# AUDIO_ETHNET.net
KiCad netlist of a schematic drawn in Altium Designer
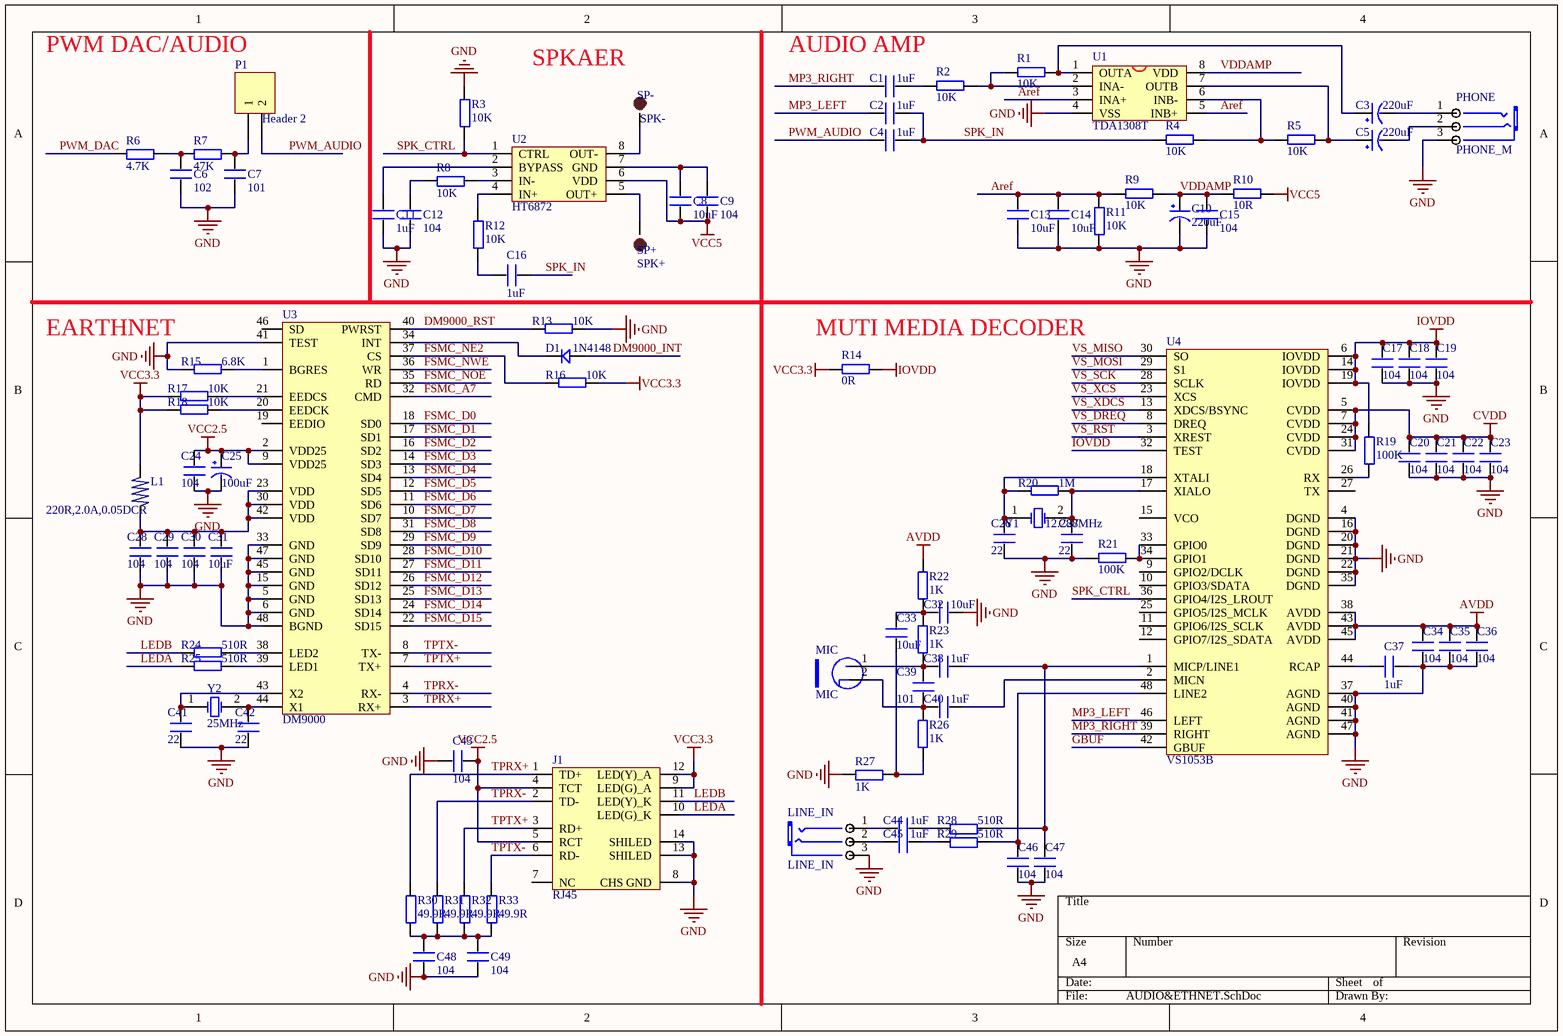
[diagram p0: AUDIO&ETHNET.SchDoc]

(export (version "E")
  (design (tool "Eeschema 10.0.6"))
  (components
    (comp (ref "C1") (value "1uF") (footprint "0603P") (libsource (lib "WarShip V3 STM32103封装库") (part "C")))
    (comp (ref "C2") (value "1uF") (footprint "0603P") (libsource (lib "WarShip V3 STM32103封装库") (part "C")))
    (comp (ref "C3")
      (value "220uF")
      (footprint "CC6.56.5")
      (libsource (lib "WarShip V3 STM32103封装库") (part "CAP"))
    )
    (comp (ref "C4") (value "1uF") (footprint "0603P") (libsource (lib "WarShip V3 STM32103封装库") (part "C")))
    (comp (ref "C5")
      (value "220uF")
      (footprint "CC6.56.5")
      (libsource (lib "WarShip V3 STM32103封装库") (part "CAP"))
    )
    (comp (ref "C6") (value "102") (footprint "0603P") (libsource (lib "WarShip V3 STM32103封装库") (part "C")))
    (comp (ref "C7") (value "101") (footprint "0603P") (libsource (lib "WarShip V3 STM32103封装库") (part "C")))
    (comp (ref "C8") (value "10uF") (footprint "0603P") (libsource (lib "WarShip V3 STM32103封装库") (part "C")))
    (comp (ref "C9") (value "104") (footprint "0603P") (libsource (lib "WarShip V3 STM32103封装库") (part "C")))
    (comp (ref "C10") (value "220uF") (footprint "CC6.56.5") (libsource (lib "") (part "CAP_1")))
    (comp (ref "C11") (value "1uF") (footprint "0603P") (libsource (lib "WarShip V3 STM32103封装库") (part "C")))
    (comp (ref "C12") (value "104") (footprint "0603P") (libsource (lib "WarShip V3 STM32103封装库") (part "C")))
    (comp (ref "C13")
      (value "10uF")
      (footprint "0603P")
      (libsource (lib "WarShip V3 STM32103封装库") (part "C"))
    )
    (comp (ref "C14")
      (value "10uF")
      (footprint "0603P")
      (libsource (lib "WarShip V3 STM32103封装库") (part "C"))
    )
    (comp (ref "C15") (value "104") (footprint "0603P") (libsource (lib "WarShip V3 STM32103封装库") (part "C")))
    (comp (ref "C16") (value "1uF") (footprint "0603P") (libsource (lib "WarShip V3 STM32103封装库") (part "C")))
    (comp (ref "C17") (value "104") (footprint "0603P") (libsource (lib "WarShip V3 STM32103封装库") (part "C")))
    (comp (ref "C18") (value "104") (footprint "0603P") (libsource (lib "WarShip V3 STM32103封装库") (part "C")))
    (comp (ref "C19") (value "104") (footprint "0603P") (libsource (lib "WarShip V3 STM32103封装库") (part "C")))
    (comp (ref "C20") (value "104") (footprint "0603P") (libsource (lib "WarShip V3 STM32103封装库") (part "C")))
    (comp (ref "C21") (value "104") (footprint "0603P") (libsource (lib "WarShip V3 STM32103封装库") (part "C")))
    (comp (ref "C22") (value "104") (footprint "0603P") (libsource (lib "WarShip V3 STM32103封装库") (part "C")))
    (comp (ref "C23") (value "104") (footprint "0603P") (libsource (lib "WarShip V3 STM32103封装库") (part "C")))
    (comp (ref "C24") (value "104") (footprint "0603P") (libsource (lib "WarShip V3 STM32103封装库") (part "C")))
    (comp (ref "C25") (value "100uF") (footprint "CC6.56.5") (libsource (lib "") (part "CAP_1")))
    (comp (ref "C26") (value "22") (footprint "0603P") (libsource (lib "WarShip V3 STM32103封装库") (part "C")))
    (comp (ref "C27") (value "22") (footprint "0603P") (libsource (lib "WarShip V3 STM32103封装库") (part "C")))
    (comp (ref "C28") (value "104") (footprint "0603P") (libsource (lib "WarShip V3 STM32103封装库") (part "C")))
    (comp (ref "C29") (value "104") (footprint "0603P") (libsource (lib "WarShip V3 STM32103封装库") (part "C")))
    (comp (ref "C30") (value "104") (footprint "0603P") (libsource (lib "WarShip V3 STM32103封装库") (part "C")))
    (comp (ref "C31")
      (value "10uF")
      (footprint "0603P")
      (libsource (lib "WarShip V3 STM32103封装库") (part "C"))
    )
    (comp (ref "C32")
      (value "10uF")
      (footprint "0603P")
      (libsource (lib "WarShip V3 STM32103封装库") (part "C"))
    )
    (comp (ref "C33")
      (value "10uF")
      (footprint "0603P")
      (libsource (lib "WarShip V3 STM32103封装库") (part "C"))
    )
    (comp (ref "C34") (value "104") (footprint "0603P") (libsource (lib "WarShip V3 STM32103封装库") (part "C")))
    (comp (ref "C35") (value "104") (footprint "0603P") (libsource (lib "WarShip V3 STM32103封装库") (part "C")))
    (comp (ref "C36") (value "104") (footprint "0603P") (libsource (lib "WarShip V3 STM32103封装库") (part "C")))
    (comp (ref "C37") (value "1uF") (footprint "0603P") (libsource (lib "WarShip V3 STM32103封装库") (part "C")))
    (comp (ref "C38") (value "1uF") (footprint "0603P") (libsource (lib "WarShip V3 STM32103封装库") (part "C")))
    (comp (ref "C39") (value "101") (footprint "0603P") (libsource (lib "WarShip V3 STM32103封装库") (part "C")))
    (comp (ref "C40") (value "1uF") (footprint "0603P") (libsource (lib "WarShip V3 STM32103封装库") (part "C")))
    (comp (ref "C41") (value "22") (footprint "0603P") (libsource (lib "WarShip V3 STM32103封装库") (part "C")))
    (comp (ref "C42") (value "22") (footprint "0603P") (libsource (lib "WarShip V3 STM32103封装库") (part "C")))
    (comp (ref "C43") (value "104") (footprint "0603P") (libsource (lib "WarShip V3 STM32103封装库") (part "C")))
    (comp (ref "C44") (value "1uF") (footprint "0603P") (libsource (lib "WarShip V3 STM32103封装库") (part "C")))
    (comp (ref "C45") (value "1uF") (footprint "0603P") (libsource (lib "WarShip V3 STM32103封装库") (part "C")))
    (comp (ref "C46") (value "104") (footprint "0603P") (libsource (lib "WarShip V3 STM32103封装库") (part "C")))
    (comp (ref "C47") (value "104") (footprint "0603P") (libsource (lib "WarShip V3 STM32103封装库") (part "C")))
    (comp (ref "C48") (value "104") (footprint "0603P") (libsource (lib "WarShip V3 STM32103封装库") (part "C")))
    (comp (ref "C49") (value "104") (footprint "0603P") (libsource (lib "WarShip V3 STM32103封装库") (part "C")))
    (comp (ref "D1")
      (value "1N4148")
      (footprint "DIODE_SOP")
      (libsource (lib "WarShip V3 STM32103封装库") (part "D"))
    )
    (comp (ref "J1")
      (value "RJ45")
      (footprint "HR911105A")
      (libsource (lib "WarShip V3 STM32103封装库") (part "HR911105"))
    )
    (comp (ref "L1")
      (value "220R,2.0A,0.05DCR")
      (footprint "0603P")
      (libsource (lib "WarShip V3 STM32103封装库") (part "L"))
    )
    (comp (ref "LINE_IN")
      (value "LINE_IN")
      (footprint "PHONE_ST")
      (libsource (lib "WarShip V3 STM32103封装库") (part "PHONE_M"))
    )
    (comp (ref "MIC")
      (value "MIC")
      (footprint "MIC-6022")
      (libsource (lib "WarShip V3 STM32103封装库") (part "MIC"))
    )
    (comp (ref "P1")
      (value "Header 2")
      (footprint "HDR1X2")
      (description "Header, 2-Pin")
      (fields (field (name "PUBLISHER") "Altium Limited"))
      (libsource (lib "WarShip V3 STM32103封装库") (part "Header 2"))
    )
    (comp (ref "PHONE") (value "PHONE_M") (footprint "PHONE_ST") (libsource (lib "") (part "PHONE_M_1")))
    (comp (ref "R1") (value "10K") (footprint "0603P") (libsource (lib "WarShip V3 STM32103封装库") (part "R")))
    (comp (ref "R2") (value "10K") (footprint "0603P") (libsource (lib "WarShip V3 STM32103封装库") (part "R")))
    (comp (ref "R3") (value "10K") (footprint "0603P") (libsource (lib "WarShip V3 STM32103封装库") (part "R")))
    (comp (ref "R4") (value "10K") (footprint "0603P") (libsource (lib "WarShip V3 STM32103封装库") (part "R")))
    (comp (ref "R5") (value "10K") (footprint "0603P") (libsource (lib "WarShip V3 STM32103封装库") (part "R")))
    (comp (ref "R6") (value "4.7K") (footprint "0603P") (libsource (lib "WarShip V3 STM32103封装库") (part "R")))
    (comp (ref "R7") (value "47K") (footprint "0603P") (libsource (lib "WarShip V3 STM32103封装库") (part "R")))
    (comp (ref "R8") (value "10K") (footprint "0603P") (libsource (lib "WarShip V3 STM32103封装库") (part "R")))
    (comp (ref "R9") (value "10K") (footprint "0603P") (libsource (lib "WarShip V3 STM32103封装库") (part "R")))
    (comp (ref "R10") (value "10R") (footprint "0603P") (libsource (lib "WarShip V3 STM32103封装库") (part "R")))
    (comp (ref "R11") (value "10K") (footprint "0603P") (libsource (lib "WarShip V3 STM32103封装库") (part "R")))
    (comp (ref "R12") (value "10K") (footprint "0603P") (libsource (lib "WarShip V3 STM32103封装库") (part "R")))
    (comp (ref "R13") (value "10K") (footprint "0603P") (libsource (lib "WarShip V3 STM32103封装库") (part "R")))
    (comp (ref "R14") (value "0R") (footprint "0603P") (libsource (lib "WarShip V3 STM32103封装库") (part "R")))
    (comp (ref "R15")
      (value "6.8K")
      (footprint "0603P")
      (libsource (lib "WarShip V3 STM32103封装库") (part "R"))
    )
    (comp (ref "R16") (value "10K") (footprint "0603P") (libsource (lib "WarShip V3 STM32103封装库") (part "R")))
    (comp (ref "R17") (value "10K") (footprint "0603P") (libsource (lib "WarShip V3 STM32103封装库") (part "R")))
    (comp (ref "R18") (value "10K") (footprint "0603P") (libsource (lib "WarShip V3 STM32103封装库") (part "R")))
    (comp (ref "R19")
      (value "100K")
      (footprint "0603P")
      (libsource (lib "WarShip V3 STM32103封装库") (part "R"))
    )
    (comp (ref "R20") (value "1M") (footprint "0603P") (libsource (lib "WarShip V3 STM32103封装库") (part "R")))
    (comp (ref "R21")
      (value "100K")
      (footprint "0603P")
      (libsource (lib "WarShip V3 STM32103封装库") (part "R"))
    )
    (comp (ref "R22") (value "1K") (footprint "0603P") (libsource (lib "WarShip V3 STM32103封装库") (part "R")))
    (comp (ref "R23") (value "1K") (footprint "0603P") (libsource (lib "WarShip V3 STM32103封装库") (part "R")))
    (comp (ref "R24")
      (value "510R")
      (footprint "0603P")
      (libsource (lib "WarShip V3 STM32103封装库") (part "R"))
    )
    (comp (ref "R25")
      (value "510R")
      (footprint "0603P")
      (libsource (lib "WarShip V3 STM32103封装库") (part "R"))
    )
    (comp (ref "R26") (value "1K") (footprint "0603P") (libsource (lib "WarShip V3 STM32103封装库") (part "R")))
    (comp (ref "R27") (value "1K") (footprint "0603P") (libsource (lib "WarShip V3 STM32103封装库") (part "R")))
    (comp (ref "R28")
      (value "510R")
      (footprint "0603P")
      (libsource (lib "WarShip V3 STM32103封装库") (part "R"))
    )
    (comp (ref "R29")
      (value "510R")
      (footprint "0603P")
      (libsource (lib "WarShip V3 STM32103封装库") (part "R"))
    )
    (comp (ref "R30")
      (value "49.9R")
      (footprint "0603P")
      (libsource (lib "WarShip V3 STM32103封装库") (part "R"))
    )
    (comp (ref "R31")
      (value "49.9R")
      (footprint "0603P")
      (libsource (lib "WarShip V3 STM32103封装库") (part "R"))
    )
    (comp (ref "R32")
      (value "49.9R")
      (footprint "0603P")
      (libsource (lib "WarShip V3 STM32103封装库") (part "R"))
    )
    (comp (ref "R33")
      (value "49.9R")
      (footprint "0603P")
      (libsource (lib "WarShip V3 STM32103封装库") (part "R"))
    )
    (comp (ref "SP+")
      (value "SPK+")
      (footprint "TP-1.5")
      (description "测试点")
      (libsource (lib "WarShip V3 STM32103封装库") (part "TEST-POINT"))
    )
    (comp (ref "SP-")
      (value "SPK-")
      (footprint "TP-1.5")
      (description "测试点")
      (libsource (lib "WarShip V3 STM32103封装库") (part "TEST-POINT"))
    )
    (comp (ref "U1")
      (value "TDA1308T")
      (footprint "SOP-8")
      (libsource (lib "WarShip V3 STM32103封装库") (part "TDA1308"))
    )
    (comp (ref "U2")
      (value "HT6872")
      (footprint "SOP-8")
      (description "HT6871")
      (libsource (lib "WarShip V3 STM32103封装库") (part "HT6871"))
    )
    (comp (ref "U3")
      (value "DM9000")
      (footprint "mTQFP48")
      (libsource (lib "WarShip V3 STM32103封装库") (part "DM9000A"))
    )
    (comp (ref "U4")
      (value "VS1053B")
      (footprint "mTQFP48")
      (libsource (lib "WarShip V3 STM32103封装库") (part "VS1053"))
    )
    (comp (ref "Y1")
      (value "12.288MHz")
      (footprint "XTAL_US")
      (description "Crystal Oscillator")
      (fields (field (name "PUBLISHER") "Altium Limited"))
      (libsource (lib "WarShip V3 STM32103封装库") (part "XTAL"))
    )
    (comp (ref "Y2")
      (value "25MHz")
      (footprint "XTAL_US")
      (description "Crystal Oscillator")
      (fields (field (name "PUBLISHER") "Altium Limited"))
      (libsource (lib "WarShip V3 STM32103封装库") (part "XTAL"))
    )
  )
  (nets
    (net (code "1") (name "/Aref") (class "Default")
      (node (ref "C13") (pin "2") (pintype "passive"))
      (node (ref "C14") (pin "2") (pintype "passive"))
      (node (ref "R11") (pin "2") (pintype "passive"))
      (node (ref "R9") (pin "2") (pintype "passive"))
      (node (ref "U1") (pin "3") (pinfunction "INA+_3") (pintype "passive"))
      (node (ref "U1") (pin "5") (pinfunction "INB+_5") (pintype "passive"))
    )
    (net (code "2") (name "/DM9000_INT") (class "Default") (node (ref "D1") (pin "1") (pintype "passive")))
    (net (code "3") (name "/DM9000_RST") (class "Default")
      (node (ref "R13") (pin "2") (pintype "passive"))
      (node (ref "U3") (pin "40") (pinfunction "PWRST_40") (pintype "passive"))
    )
    (net (code "4") (name "/FSMC_A7") (class "Default")
      (node (ref "U3") (pin "32") (pinfunction "CMD_32") (pintype "passive"))
    )
    (net (code "5") (name "/FSMC_D0") (class "Default")
      (node (ref "U3") (pin "18") (pinfunction "SD0_18") (pintype "passive"))
    )
    (net (code "6") (name "/FSMC_D1") (class "Default")
      (node (ref "U3") (pin "17") (pinfunction "SD1_17") (pintype "passive"))
    )
    (net (code "7") (name "/FSMC_D2") (class "Default")
      (node (ref "U3") (pin "16") (pinfunction "SD2_16") (pintype "passive"))
    )
    (net (code "8") (name "/FSMC_D3") (class "Default")
      (node (ref "U3") (pin "14") (pinfunction "SD3_14") (pintype "passive"))
    )
    (net (code "9") (name "/FSMC_D4") (class "Default")
      (node (ref "U3") (pin "13") (pinfunction "SD4_13") (pintype "passive"))
    )
    (net (code "10") (name "/FSMC_D5") (class "Default")
      (node (ref "U3") (pin "12") (pinfunction "SD5_12") (pintype "passive"))
    )
    (net (code "11") (name "/FSMC_D6") (class "Default")
      (node (ref "U3") (pin "11") (pinfunction "SD6_11") (pintype "passive"))
    )
    (net (code "12") (name "/FSMC_D7") (class "Default")
      (node (ref "U3") (pin "10") (pinfunction "SD7_10") (pintype "passive"))
    )
    (net (code "13") (name "/FSMC_D8") (class "Default")
      (node (ref "U3") (pin "31") (pinfunction "SD8_31") (pintype "passive"))
    )
    (net (code "14") (name "/FSMC_D9") (class "Default")
      (node (ref "U3") (pin "29") (pinfunction "SD9_29") (pintype "passive"))
    )
    (net (code "15") (name "/FSMC_D10") (class "Default")
      (node (ref "U3") (pin "28") (pinfunction "SD10_28") (pintype "passive"))
    )
    (net (code "16") (name "/FSMC_D11") (class "Default")
      (node (ref "U3") (pin "27") (pinfunction "SD11_27") (pintype "passive"))
    )
    (net (code "17") (name "/FSMC_D12") (class "Default")
      (node (ref "U3") (pin "26") (pinfunction "SD12_26") (pintype "passive"))
    )
    (net (code "18") (name "/FSMC_D13") (class "Default")
      (node (ref "U3") (pin "25") (pinfunction "SD13_25") (pintype "passive"))
    )
    (net (code "19") (name "/FSMC_D14") (class "Default")
      (node (ref "U3") (pin "24") (pinfunction "SD14_24") (pintype "passive"))
    )
    (net (code "20") (name "/FSMC_D15") (class "Default")
      (node (ref "U3") (pin "22") (pinfunction "SD15_22") (pintype "passive"))
    )
    (net (code "21") (name "/FSMC_NE2") (class "Default")
      (node (ref "R16") (pin "2") (pintype "passive"))
      (node (ref "U3") (pin "37") (pinfunction "CS_37") (pintype "passive"))
    )
    (net (code "22") (name "/FSMC_NOE") (class "Default")
      (node (ref "U3") (pin "35") (pinfunction "RD_35") (pintype "passive"))
    )
    (net (code "23") (name "/FSMC_NWE") (class "Default")
      (node (ref "U3") (pin "36") (pinfunction "WR_36") (pintype "passive"))
    )
    (net (code "24") (name "/GBUF") (class "Default")
      (node (ref "U4") (pin "42") (pinfunction "GBUF_42") (pintype "passive"))
    )
    (net (code "25") (name "/LEDA") (class "Default")
      (node (ref "J1") (pin "10") (pinfunction "LED(G)_K_10") (pintype "passive"))
      (node (ref "R25") (pin "2") (pintype "passive"))
    )
    (net (code "26") (name "/LEDB") (class "Default")
      (node (ref "J1") (pin "11") (pinfunction "LED(Y)_K_11") (pintype "passive"))
      (node (ref "R24") (pin "2") (pintype "passive"))
    )
    (net (code "27") (name "/MP3_LEFT") (class "Default")
      (node (ref "C2") (pin "2") (pintype "passive"))
      (node (ref "U4") (pin "46") (pinfunction "LEFT_46") (pintype "passive"))
    )
    (net (code "28") (name "/MP3_RIGHT") (class "Default")
      (node (ref "C1") (pin "2") (pintype "passive"))
      (node (ref "U4") (pin "39") (pinfunction "RIGHT_39") (pintype "passive"))
    )
    (net (code "29") (name "/PWM_AUDIO") (class "Default")
      (node (ref "C4") (pin "2") (pintype "passive"))
      (node (ref "P1") (pin "2") (pinfunction "2_2") (pintype "passive"))
    )
    (net (code "30") (name "/PWM_DAC") (class "Default") (node (ref "R6") (pin "1") (pintype "passive")))
    (net (code "31") (name "/SPK_CTRL") (class "Default")
      (node (ref "R3") (pin "1") (pintype "passive"))
      (node (ref "U2") (pin "1") (pinfunction "CTRL_1") (pintype "passive"))
      (node (ref "U4") (pin "36") (pinfunction "GPIO4/I2S_LROUT_36") (pintype "passive"))
    )
    (net (code "32") (name "/SPK_IN") (class "Default")
      (node (ref "C16") (pin "1") (pintype "passive"))
      (node (ref "C2") (pin "1") (pintype "passive"))
      (node (ref "C4") (pin "1") (pintype "passive"))
      (node (ref "R4") (pin "2") (pintype "passive"))
    )
    (net (code "33") (name "/TPRX+") (class "Default")
      (node (ref "J1") (pin "1") (pinfunction "TD+_1") (pintype "passive"))
      (node (ref "R30") (pin "2") (pintype "passive"))
      (node (ref "U3") (pin "3") (pinfunction "RX+_3") (pintype "passive"))
    )
    (net (code "34") (name "/TPRX-") (class "Default")
      (node (ref "J1") (pin "2") (pinfunction "TD-_2") (pintype "passive"))
      (node (ref "R31") (pin "2") (pintype "passive"))
      (node (ref "U3") (pin "4") (pinfunction "RX-_4") (pintype "passive"))
    )
    (net (code "35") (name "/TPTX+") (class "Default")
      (node (ref "J1") (pin "3") (pinfunction "RD+_3") (pintype "passive"))
      (node (ref "R32") (pin "2") (pintype "passive"))
      (node (ref "U3") (pin "7") (pinfunction "TX+_7") (pintype "passive"))
    )
    (net (code "36") (name "/TPTX-") (class "Default")
      (node (ref "J1") (pin "6") (pinfunction "RD-_6") (pintype "passive"))
      (node (ref "R33") (pin "2") (pintype "passive"))
      (node (ref "U3") (pin "8") (pinfunction "TX-_8") (pintype "passive"))
    )
    (net (code "37") (name "/VDDAMP") (class "Default")
      (node (ref "C10") (pin "1") (pinfunction "VCC_1") (pintype "passive"))
      (node (ref "C15") (pin "2") (pintype "passive"))
      (node (ref "R10") (pin "2") (pintype "passive"))
      (node (ref "R9") (pin "1") (pintype "passive"))
      (node (ref "U1") (pin "8") (pinfunction "VDD_8") (pintype "passive"))
    )
    (net (code "38") (name "/VS_DREQ") (class "Default")
      (node (ref "U4") (pin "8") (pinfunction "DREQ_8") (pintype "passive"))
    )
    (net (code "39") (name "/VS_MISO") (class "Default")
      (node (ref "U4") (pin "30") (pinfunction "SO_30") (pintype "passive"))
    )
    (net (code "40") (name "/VS_MOSI") (class "Default")
      (node (ref "U4") (pin "29") (pinfunction "S1_29") (pintype "passive"))
    )
    (net (code "41") (name "/VS_RST") (class "Default")
      (node (ref "U4") (pin "3") (pinfunction "XREST_3") (pintype "passive"))
    )
    (net (code "42") (name "/VS_SCK") (class "Default")
      (node (ref "U4") (pin "28") (pinfunction "SCLK_28") (pintype "passive"))
    )
    (net (code "43") (name "/VS_XCS") (class "Default")
      (node (ref "U4") (pin "23") (pinfunction "XCS_23") (pintype "passive"))
    )
    (net (code "44") (name "/VS_XDCS") (class "Default")
      (node (ref "U4") (pin "13") (pinfunction "XDCS/BSYNC_13") (pintype "passive"))
    )
    (net (code "45") (name "AVDD") (class "Default")
      (node (ref "C34") (pin "1") (pintype "passive"))
      (node (ref "C35") (pin "1") (pintype "passive"))
      (node (ref "C36") (pin "1") (pintype "passive"))
      (node (ref "R22") (pin "1") (pintype "passive"))
      (node (ref "U4") (pin "38") (pinfunction "AVDD_38") (pintype "passive"))
      (node (ref "U4") (pin "43") (pinfunction "AVDD_43") (pintype "passive"))
      (node (ref "U4") (pin "45") (pinfunction "AVDD_45") (pintype "passive"))
    )
    (net (code "46") (name "CVDD") (class "Default")
      (node (ref "C20") (pin "1") (pintype "passive"))
      (node (ref "C21") (pin "1") (pintype "passive"))
      (node (ref "C22") (pin "1") (pintype "passive"))
      (node (ref "C23") (pin "1") (pintype "passive"))
      (node (ref "U4") (pin "24") (pinfunction "CVDD_24") (pintype "passive"))
      (node (ref "U4") (pin "31") (pinfunction "CVDD_31") (pintype "passive"))
      (node (ref "U4") (pin "5") (pinfunction "CVDD_5") (pintype "passive"))
      (node (ref "U4") (pin "7") (pinfunction "CVDD_7") (pintype "passive"))
    )
    (net (code "47") (name "GND") (class "Default")
      (node (ref "C10") (pin "2") (pinfunction "GND_2") (pintype "passive"))
      (node (ref "C11") (pin "1") (pintype "passive"))
      (node (ref "C12") (pin "1") (pintype "passive"))
      (node (ref "C13") (pin "1") (pintype "passive"))
      (node (ref "C14") (pin "1") (pintype "passive"))
      (node (ref "C15") (pin "1") (pintype "passive"))
      (node (ref "C17") (pin "2") (pintype "passive"))
      (node (ref "C18") (pin "2") (pintype "passive"))
      (node (ref "C19") (pin "2") (pintype "passive"))
      (node (ref "C20") (pin "2") (pintype "passive"))
      (node (ref "C21") (pin "2") (pintype "passive"))
      (node (ref "C22") (pin "2") (pintype "passive"))
      (node (ref "C23") (pin "2") (pintype "passive"))
      (node (ref "C24") (pin "1") (pintype "passive"))
      (node (ref "C25") (pin "2") (pinfunction "GND_2") (pintype "passive"))
      (node (ref "C26") (pin "1") (pintype "passive"))
      (node (ref "C27") (pin "1") (pintype "passive"))
      (node (ref "C28") (pin "1") (pintype "passive"))
      (node (ref "C29") (pin "1") (pintype "passive"))
      (node (ref "C30") (pin "1") (pintype "passive"))
      (node (ref "C31") (pin "1") (pintype "passive"))
      (node (ref "C32") (pin "2") (pintype "passive"))
      (node (ref "C34") (pin "2") (pintype "passive"))
      (node (ref "C35") (pin "2") (pintype "passive"))
      (node (ref "C36") (pin "2") (pintype "passive"))
      (node (ref "C37") (pin "2") (pintype "passive"))
      (node (ref "C41") (pin "1") (pintype "passive"))
      (node (ref "C42") (pin "1") (pintype "passive"))
      (node (ref "C43") (pin "2") (pintype "passive"))
      (node (ref "C46") (pin "2") (pintype "passive"))
      (node (ref "C47") (pin "2") (pintype "passive"))
      (node (ref "C48") (pin "2") (pintype "passive"))
      (node (ref "C49") (pin "2") (pintype "passive"))
      (node (ref "C6") (pin "1") (pintype "passive"))
      (node (ref "C7") (pin "1") (pintype "passive"))
      (node (ref "J1") (pin "13") (pinfunction "SHILED_13") (pintype "passive"))
      (node (ref "J1") (pin "14") (pinfunction "SHILED_14") (pintype "passive"))
      (node (ref "J1") (pin "8") (pinfunction "CHS_GND_8") (pintype "passive"))
      (node (ref "LINE_IN") (pin "3") (pinfunction "COM_3") (pintype "passive"))
      (node (ref "PHONE") (pin "3") (pinfunction "COM_3") (pintype "passive"))
      (node (ref "R11") (pin "1") (pintype "passive"))
      (node (ref "R13") (pin "1") (pintype "passive"))
      (node (ref "R15") (pin "2") (pintype "passive"))
      (node (ref "R21") (pin "2") (pintype "passive"))
      (node (ref "R27") (pin "1") (pintype "passive"))
      (node (ref "R3") (pin "2") (pintype "passive"))
      (node (ref "U1") (pin "4") (pinfunction "VSS_4") (pintype "passive"))
      (node (ref "U3") (pin "15") (pinfunction "GND_15") (pintype "passive"))
      (node (ref "U3") (pin "33") (pinfunction "GND_33") (pintype "passive"))
      (node (ref "U3") (pin "41") (pinfunction "TEST_41") (pintype "passive"))
      (node (ref "U3") (pin "45") (pinfunction "GND_45") (pintype "passive"))
      (node (ref "U3") (pin "47") (pinfunction "GND_47") (pintype "passive"))
      (node (ref "U3") (pin "48") (pinfunction "BGND_48") (pintype "passive"))
      (node (ref "U3") (pin "5") (pinfunction "GND_5") (pintype "passive"))
      (node (ref "U3") (pin "6") (pinfunction "GND_6") (pintype "passive"))
      (node (ref "U4") (pin "16") (pinfunction "DGND_16") (pintype "passive"))
      (node (ref "U4") (pin "20") (pinfunction "DGND_20") (pintype "passive"))
      (node (ref "U4") (pin "21") (pinfunction "DGND_21") (pintype "passive"))
      (node (ref "U4") (pin "22") (pinfunction "DGND_22") (pintype "passive"))
      (node (ref "U4") (pin "35") (pinfunction "DGND_35") (pintype "passive"))
      (node (ref "U4") (pin "37") (pinfunction "AGND_37") (pintype "passive"))
      (node (ref "U4") (pin "4") (pinfunction "DGND_4") (pintype "passive"))
      (node (ref "U4") (pin "40") (pinfunction "AGND_40") (pintype "passive"))
      (node (ref "U4") (pin "41") (pinfunction "AGND_41") (pintype "passive"))
      (node (ref "U4") (pin "47") (pinfunction "AGND_47") (pintype "passive"))
    )
    (net (code "48") (name "IOVDD") (class "Default")
      (node (ref "C17") (pin "1") (pintype "passive"))
      (node (ref "C18") (pin "1") (pintype "passive"))
      (node (ref "C19") (pin "1") (pintype "passive"))
      (node (ref "R14") (pin "1") (pintype "passive"))
      (node (ref "R19") (pin "2") (pintype "passive"))
      (node (ref "U4") (pin "14") (pinfunction "IOVDD_14") (pintype "passive"))
      (node (ref "U4") (pin "19") (pinfunction "IOVDD_19") (pintype "passive"))
      (node (ref "U4") (pin "32") (pinfunction "TEST_32") (pintype "passive"))
      (node (ref "U4") (pin "6") (pinfunction "IOVDD_6") (pintype "passive"))
    )
    (net (code "49") (name "Net-(C1-Pad1)") (class "Default")
      (node (ref "C1") (pin "1") (pintype "passive"))
      (node (ref "R2") (pin "2") (pintype "passive"))
    )
    (net (code "50") (name "Net-(C3-GND)") (class "Default")
      (node (ref "C3") (pin "2") (pinfunction "GND_2") (pintype "passive"))
      (node (ref "PHONE") (pin "1") (pinfunction "CHL_1") (pintype "passive"))
    )
    (net (code "51") (name "Net-(C3-VCC)") (class "Default")
      (node (ref "C3") (pin "1") (pinfunction "VCC_1") (pintype "passive"))
      (node (ref "R1") (pin "1") (pintype "passive"))
      (node (ref "U1") (pin "1") (pinfunction "OUTA_1") (pintype "passive"))
    )
    (net (code "52") (name "Net-(C5-GND)") (class "Default")
      (node (ref "C5") (pin "2") (pinfunction "GND_2") (pintype "passive"))
      (node (ref "PHONE") (pin "2") (pinfunction "CHR_2") (pintype "passive"))
    )
    (net (code "53") (name "Net-(C5-VCC)") (class "Default")
      (node (ref "C5") (pin "1") (pinfunction "VCC_1") (pintype "passive"))
      (node (ref "R5") (pin "1") (pintype "passive"))
      (node (ref "U1") (pin "7") (pinfunction "OUTB_7") (pintype "passive"))
    )
    (net (code "54") (name "Net-(C6-Pad2)") (class "Default")
      (node (ref "C6") (pin "2") (pintype "passive"))
      (node (ref "R6") (pin "2") (pintype "passive"))
      (node (ref "R7") (pin "1") (pintype "passive"))
    )
    (net (code "55") (name "Net-(C7-Pad2)") (class "Default")
      (node (ref "C7") (pin "2") (pintype "passive"))
      (node (ref "P1") (pin "1") (pinfunction "1_1") (pintype "passive"))
      (node (ref "R7") (pin "2") (pintype "passive"))
    )
    (net (code "56") (name "Net-(C12-Pad2)") (class "Default")
      (node (ref "C12") (pin "2") (pintype "passive"))
      (node (ref "R8") (pin "1") (pintype "passive"))
    )
    (net (code "57") (name "Net-(C16-Pad2)") (class "Default")
      (node (ref "C16") (pin "2") (pintype "passive"))
      (node (ref "R12") (pin "1") (pintype "passive"))
    )
    (net (code "58") (name "Net-(C28-Pad2)") (class "Default")
      (node (ref "C28") (pin "2") (pintype "passive"))
      (node (ref "C29") (pin "2") (pintype "passive"))
      (node (ref "C30") (pin "2") (pintype "passive"))
      (node (ref "C31") (pin "2") (pintype "passive"))
      (node (ref "L1") (pin "1") (pintype "passive"))
      (node (ref "U3") (pin "23") (pinfunction "VDD_23") (pintype "passive"))
      (node (ref "U3") (pin "30") (pinfunction "VDD_30") (pintype "passive"))
      (node (ref "U3") (pin "42") (pinfunction "VDD_42") (pintype "passive"))
    )
    (net (code "59") (name "Net-(C32-Pad1)") (class "Default")
      (node (ref "C32") (pin "1") (pintype "passive"))
      (node (ref "C33") (pin "1") (pintype "passive"))
      (node (ref "R22") (pin "2") (pintype "passive"))
      (node (ref "R23") (pin "1") (pintype "passive"))
    )
    (net (code "60") (name "Net-(C33-Pad2)") (class "Default")
      (node (ref "C33") (pin "2") (pintype "passive"))
      (node (ref "R26") (pin "2") (pintype "passive"))
      (node (ref "R27") (pin "2") (pintype "passive"))
    )
    (net (code "61") (name "Net-(C44-Pad2)") (class "Default")
      (node (ref "C44") (pin "2") (pintype "passive"))
      (node (ref "R28") (pin "1") (pintype "passive"))
    )
    (net (code "62") (name "Net-(C45-Pad2)") (class "Default")
      (node (ref "C45") (pin "2") (pintype "passive"))
      (node (ref "R29") (pin "1") (pintype "passive"))
    )
    (net (code "63") (name "Net-(C48-Pad1)") (class "Default")
      (node (ref "C48") (pin "1") (pintype "passive"))
      (node (ref "C49") (pin "1") (pintype "passive"))
      (node (ref "R30") (pin "1") (pintype "passive"))
      (node (ref "R31") (pin "1") (pintype "passive"))
      (node (ref "R32") (pin "1") (pintype "passive"))
      (node (ref "R33") (pin "1") (pintype "passive"))
    )
    (net (code "64") (name "Net-(LINE_IN-CHL)") (class "Default")
      (node (ref "C44") (pin "1") (pintype "passive"))
      (node (ref "LINE_IN") (pin "1") (pinfunction "CHL_1") (pintype "passive"))
    )
    (net (code "65") (name "Net-(LINE_IN-CHR)") (class "Default")
      (node (ref "C45") (pin "1") (pintype "passive"))
      (node (ref "LINE_IN") (pin "2") (pinfunction "CHR_2") (pintype "passive"))
    )
    (net (code "66") (name "Net-(MIC-GND)") (class "Default")
      (node (ref "C39") (pin "2") (pintype "passive"))
      (node (ref "C40") (pin "1") (pintype "passive"))
      (node (ref "MIC") (pin "2") (pinfunction "GND_2") (pintype "passive"))
      (node (ref "R26") (pin "1") (pintype "passive"))
    )
    (net (code "67") (name "Net-(MIC-VCC)") (class "Default")
      (node (ref "C38") (pin "1") (pintype "passive"))
      (node (ref "C39") (pin "1") (pintype "passive"))
      (node (ref "MIC") (pin "1") (pinfunction "VCC_1") (pintype "passive"))
      (node (ref "R23") (pin "2") (pintype "passive"))
    )
    (net (code "68") (name "Net-(U1-INA-)") (class "Default")
      (node (ref "R1") (pin "2") (pintype "passive"))
      (node (ref "R2") (pin "1") (pintype "passive"))
      (node (ref "U1") (pin "2") (pinfunction "INA-_2") (pintype "passive"))
    )
    (net (code "69") (name "Net-(U1-INB-)") (class "Default")
      (node (ref "R4") (pin "1") (pintype "passive"))
      (node (ref "R5") (pin "2") (pintype "passive"))
      (node (ref "U1") (pin "6") (pinfunction "INB-_6") (pintype "passive"))
    )
    (net (code "70") (name "Net-(U2-BYPASS)") (class "Default")
      (node (ref "C11") (pin "2") (pintype "passive"))
      (node (ref "U2") (pin "2") (pinfunction "BYPASS_2") (pintype "passive"))
    )
    (net (code "71") (name "Net-(U2-GND)") (class "Default")
      (node (ref "C8") (pin "2") (pintype "passive"))
      (node (ref "C9") (pin "2") (pintype "passive"))
      (node (ref "U2") (pin "7") (pinfunction "GND_7") (pintype "passive"))
    )
    (net (code "72") (name "Net-(U2-IN+)") (class "Default")
      (node (ref "R12") (pin "2") (pintype "passive"))
      (node (ref "U2") (pin "4") (pinfunction "IN+_4") (pintype "passive"))
    )
    (net (code "73") (name "Net-(U2-IN-)") (class "Default")
      (node (ref "R8") (pin "2") (pintype "passive"))
      (node (ref "U2") (pin "3") (pinfunction "IN-_3") (pintype "passive"))
    )
    (net (code "74") (name "Net-(U2-OUT+)") (class "Default")
      (node (ref "SP+") (pin "1") (pinfunction "1_1") (pintype "passive"))
      (node (ref "U2") (pin "5") (pinfunction "OUT+_5") (pintype "passive"))
    )
    (net (code "75") (name "Net-(U2-OUT-)") (class "Default")
      (node (ref "SP-") (pin "1") (pinfunction "1_1") (pintype "passive"))
      (node (ref "U2") (pin "8") (pinfunction "OUT-_8") (pintype "passive"))
    )
    (net (code "76") (name "Net-(U3-BGRES)") (class "Default")
      (node (ref "R15") (pin "1") (pintype "passive"))
      (node (ref "U3") (pin "1") (pinfunction "BGRES_1") (pintype "passive"))
    )
    (net (code "77") (name "Net-(U3-EEDCK)") (class "Default")
      (node (ref "R18") (pin "1") (pintype "passive"))
      (node (ref "U3") (pin "20") (pinfunction "EEDCK_20") (pintype "passive"))
    )
    (net (code "78") (name "Net-(U3-EEDCS)") (class "Default")
      (node (ref "R17") (pin "1") (pintype "passive"))
      (node (ref "U3") (pin "21") (pinfunction "EEDCS_21") (pintype "passive"))
    )
    (net (code "79") (name "Net-(U3-INT)") (class "Default")
      (node (ref "D1") (pin "2") (pintype "passive"))
      (node (ref "U3") (pin "34") (pinfunction "INT_34") (pintype "passive"))
    )
    (net (code "80") (name "Net-(U3-LED1)") (class "Default")
      (node (ref "R25") (pin "1") (pintype "passive"))
      (node (ref "U3") (pin "39") (pinfunction "LED1_39") (pintype "passive"))
    )
    (net (code "81") (name "Net-(U3-LED2)") (class "Default")
      (node (ref "R24") (pin "1") (pintype "passive"))
      (node (ref "U3") (pin "38") (pinfunction "LED2_38") (pintype "passive"))
    )
    (net (code "82") (name "Net-(U3-X1)") (class "Default")
      (node (ref "C42") (pin "2") (pintype "passive"))
      (node (ref "U3") (pin "44") (pinfunction "X1_44") (pintype "passive"))
      (node (ref "Y2") (pin "2") (pinfunction "OSC2_2") (pintype "passive"))
    )
    (net (code "83") (name "Net-(U3-X2)") (class "Default")
      (node (ref "C41") (pin "2") (pintype "passive"))
      (node (ref "U3") (pin "43") (pinfunction "X2_43") (pintype "passive"))
      (node (ref "Y2") (pin "1") (pinfunction "OSC1_1") (pintype "passive"))
    )
    (net (code "84") (name "Net-(U4-GPIO0)") (class "Default")
      (node (ref "R21") (pin "1") (pintype "passive"))
      (node (ref "U4") (pin "33") (pinfunction "GPIO0_33") (pintype "passive"))
      (node (ref "U4") (pin "34") (pinfunction "GPIO1_34") (pintype "passive"))
    )
    (net (code "85") (name "Net-(U4-LINE2)") (class "Default")
      (node (ref "C46") (pin "1") (pintype "passive"))
      (node (ref "R29") (pin "2") (pintype "passive"))
      (node (ref "U4") (pin "48") (pinfunction "LINE2_48") (pintype "passive"))
    )
    (net (code "86") (name "Net-(U4-MICN)") (class "Default")
      (node (ref "C40") (pin "2") (pintype "passive"))
      (node (ref "U4") (pin "2") (pinfunction "MICN_2") (pintype "passive"))
    )
    (net (code "87") (name "Net-(U4-MICP{slash}LINE1)") (class "Default")
      (node (ref "C38") (pin "2") (pintype "passive"))
      (node (ref "C47") (pin "1") (pintype "passive"))
      (node (ref "R28") (pin "2") (pintype "passive"))
      (node (ref "U4") (pin "1") (pinfunction "MICP/LINE1_1") (pintype "passive"))
    )
    (net (code "88") (name "Net-(U4-RCAP)") (class "Default")
      (node (ref "C37") (pin "1") (pintype "passive"))
      (node (ref "U4") (pin "44") (pinfunction "RCAP_44") (pintype "passive"))
    )
    (net (code "89") (name "Net-(U4-RX)") (class "Default")
      (node (ref "R19") (pin "1") (pintype "passive"))
      (node (ref "U4") (pin "26") (pinfunction "RX_26") (pintype "passive"))
    )
    (net (code "90") (name "Net-(U4-XIALO)") (class "Default")
      (node (ref "C27") (pin "2") (pintype "passive"))
      (node (ref "R20") (pin "1") (pintype "passive"))
      (node (ref "U4") (pin "17") (pinfunction "XIALO_17") (pintype "passive"))
      (node (ref "Y1") (pin "2") (pinfunction "OSC2_2") (pintype "passive"))
    )
    (net (code "91") (name "Net-(U4-XTALI)") (class "Default")
      (node (ref "C26") (pin "2") (pintype "passive"))
      (node (ref "R20") (pin "2") (pintype "passive"))
      (node (ref "U4") (pin "18") (pinfunction "XTALI_18") (pintype "passive"))
      (node (ref "Y1") (pin "1") (pinfunction "OSC1_1") (pintype "passive"))
    )
    (net (code "92") (name "VCC2.5") (class "Default")
      (node (ref "C24") (pin "2") (pintype "passive"))
      (node (ref "C25") (pin "1") (pinfunction "VCC_1") (pintype "passive"))
      (node (ref "C43") (pin "1") (pintype "passive"))
      (node (ref "J1") (pin "4") (pinfunction "TCT_4") (pintype "passive"))
      (node (ref "J1") (pin "5") (pinfunction "RCT_5") (pintype "passive"))
      (node (ref "U3") (pin "2") (pinfunction "VDD25_2") (pintype "passive"))
      (node (ref "U3") (pin "9") (pinfunction "VDD25_9") (pintype "passive"))
    )
    (net (code "93") (name "VCC3.3") (class "Default")
      (node (ref "J1") (pin "12") (pinfunction "LED(Y)_A_12") (pintype "passive"))
      (node (ref "J1") (pin "9") (pinfunction "LED(G)_A_9") (pintype "passive"))
      (node (ref "L1") (pin "2") (pintype "passive"))
      (node (ref "R14") (pin "2") (pintype "passive"))
      (node (ref "R16") (pin "1") (pintype "passive"))
      (node (ref "R17") (pin "2") (pintype "passive"))
      (node (ref "R18") (pin "2") (pintype "passive"))
    )
    (net (code "94") (name "VCC5") (class "Default")
      (node (ref "C8") (pin "1") (pintype "passive"))
      (node (ref "C9") (pin "1") (pintype "passive"))
      (node (ref "R10") (pin "1") (pintype "passive"))
      (node (ref "U2") (pin "6") (pinfunction "VDD_6") (pintype "passive"))
    )
    (net (code "95") (name "unconnected-(J1-NC-Pad7)") (class "Default")
      (node (ref "J1") (pin "7") (pinfunction "NC_7") (pintype "passive"))
    )
    (net (code "96") (name "unconnected-(U3-EEDIO-Pad19)") (class "Default")
      (node (ref "U3") (pin "19") (pinfunction "EEDIO_19") (pintype "passive"))
    )
    (net (code "97") (name "unconnected-(U3-SD-Pad46)") (class "Default")
      (node (ref "U3") (pin "46") (pinfunction "SD_46") (pintype "passive"))
    )
    (net (code "98") (name "unconnected-(U4-GPIO2{slash}DCLK-Pad9)") (class "Default")
      (node (ref "U4") (pin "9") (pinfunction "GPIO2/DCLK_9") (pintype "passive"))
    )
    (net (code "99") (name "unconnected-(U4-GPIO3{slash}SDATA-Pad10)") (class "Default")
      (node (ref "U4") (pin "10") (pinfunction "GPIO3/SDATA_10") (pintype "passive"))
    )
    (net (code "100") (name "unconnected-(U4-GPIO5{slash}I2S_MCLK-Pad25)") (class "Default")
      (node (ref "U4") (pin "25") (pinfunction "GPIO5/I2S_MCLK_25") (pintype "passive"))
    )
    (net (code "101") (name "unconnected-(U4-GPIO6{slash}I2S_SCLK-Pad11)") (class "Default")
      (node (ref "U4") (pin "11") (pinfunction "GPIO6/I2S_SCLK_11") (pintype "passive"))
    )
    (net (code "102") (name "unconnected-(U4-GPIO7{slash}I2S_SDATA-Pad12)") (class "Default")
      (node (ref "U4") (pin "12") (pinfunction "GPIO7/I2S_SDATA_12") (pintype "passive"))
    )
    (net (code "103") (name "unconnected-(U4-TX-Pad27)") (class "Default")
      (node (ref "U4") (pin "27") (pinfunction "TX_27") (pintype "passive"))
    )
    (net (code "104") (name "unconnected-(U4-VCO-Pad15)") (class "Default")
      (node (ref "U4") (pin "15") (pinfunction "VCO_15") (pintype "passive"))
    )
  )
)
